# ZX_Gesture_Sensor_SMD_v02.net
KiCad netlist of a schematic drawn in EAGLE
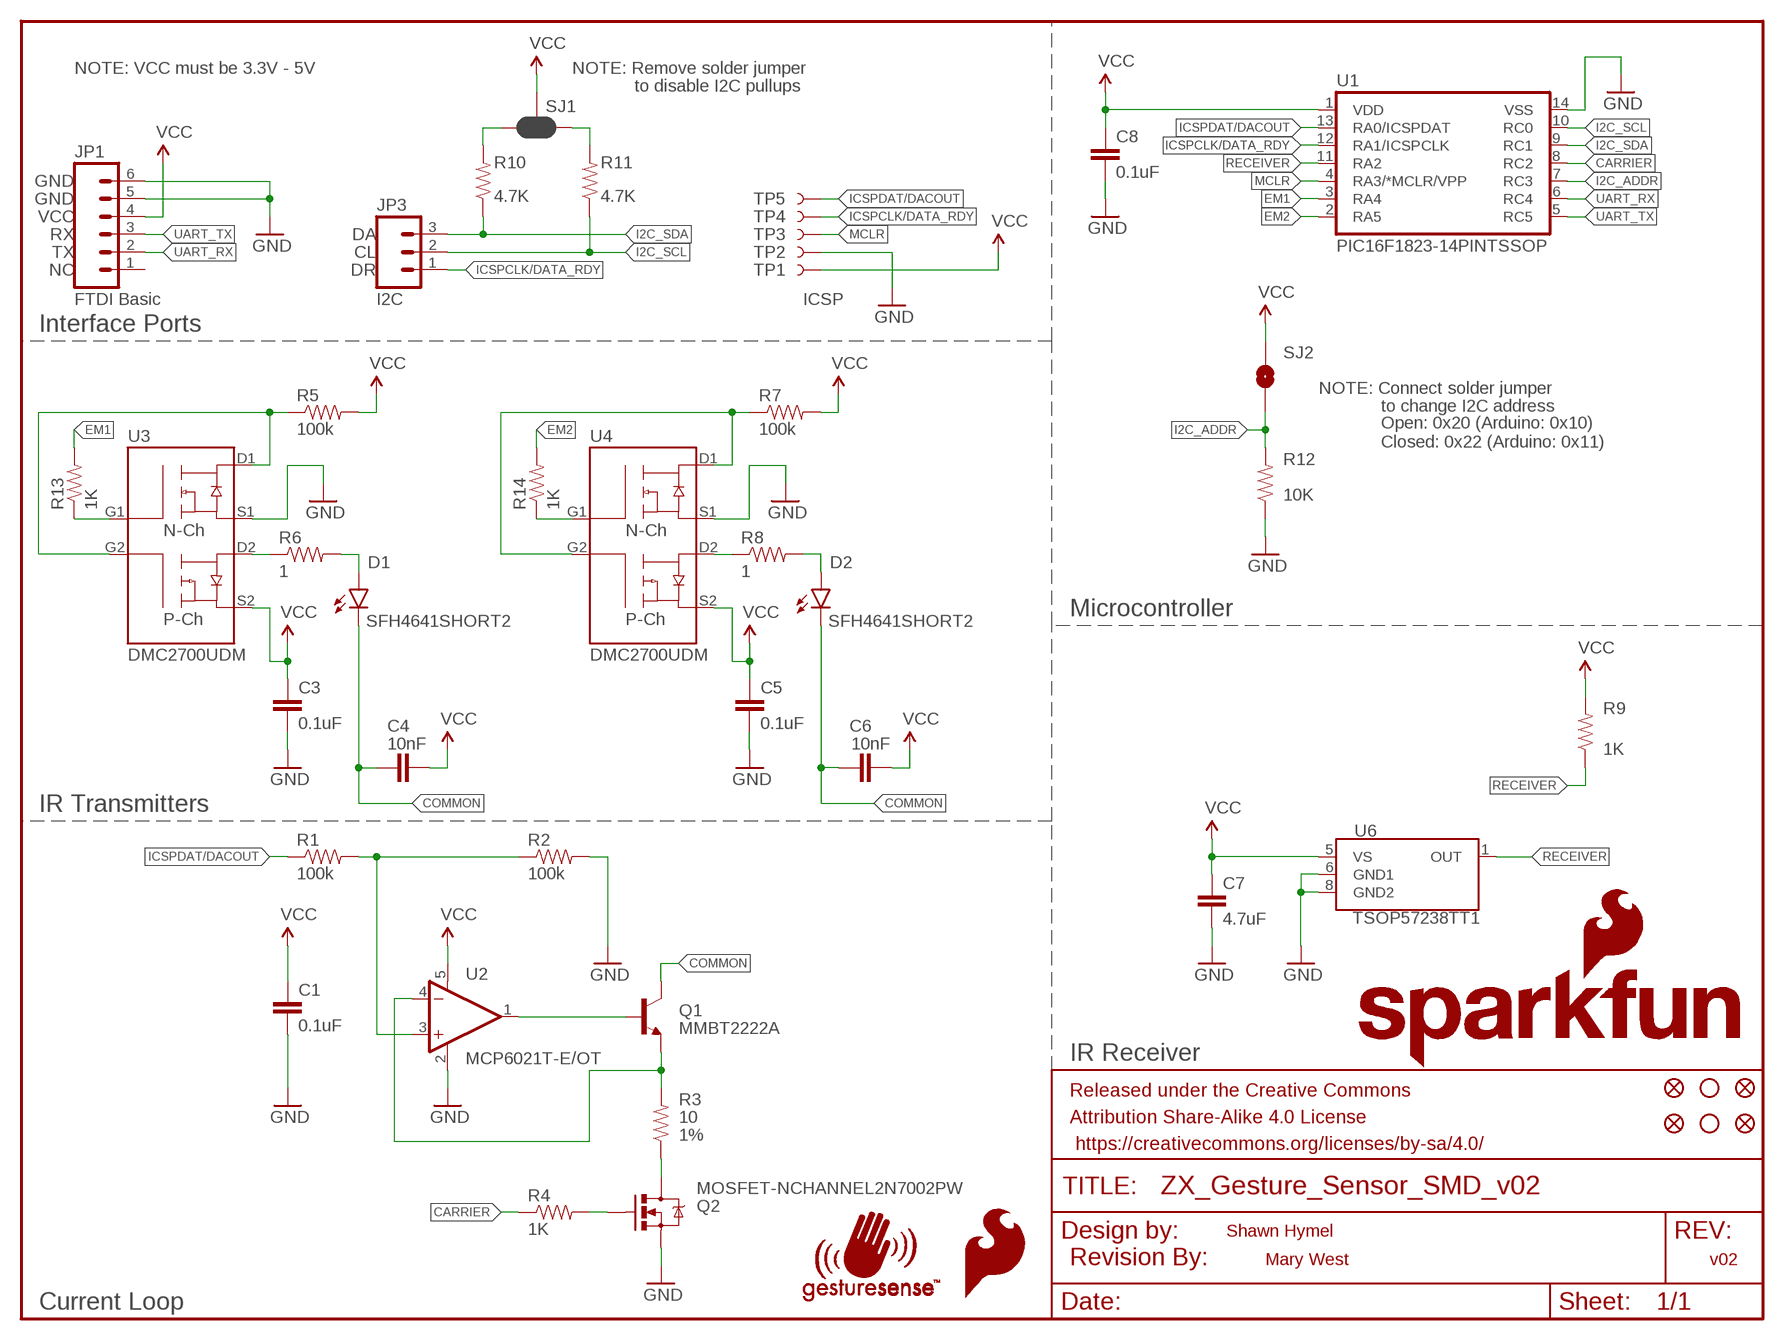
[diagram p0: schematic, sheet 1]

(export (version "E")
  (design (tool "Eeschema 10.0.6"))
  (components
    (comp (ref "C1")
      (value "0.1uF")
      (footprint "eagle-import:0603-CAP")
      (libsource (lib "eagle-import") (part "0.1UF-25V(+80/-20%)(0603)"))
    )
    (comp (ref "C3")
      (value "0.1uF")
      (footprint "eagle-import:0603-CAP")
      (libsource (lib "eagle-import") (part "0.1UF-25V(+80/-20%)(0603)"))
    )
    (comp (ref "C4")
      (value "10nF")
      (footprint "eagle-import:0603-CAP")
      (libsource (lib "eagle-import") (part "10NF/10000PF-50V-10%(0603)"))
    )
    (comp (ref "C5")
      (value "0.1uF")
      (footprint "eagle-import:0603-CAP")
      (libsource (lib "eagle-import") (part "0.1UF-25V(+80/-20%)(0603)"))
    )
    (comp (ref "C6")
      (value "10nF")
      (footprint "eagle-import:0603-CAP")
      (libsource (lib "eagle-import") (part "10NF/10000PF-50V-10%(0603)"))
    )
    (comp (ref "C7")
      (value "4.7uF")
      (footprint "eagle-import:0603-CAP")
      (libsource (lib "eagle-import") (part "4.7UF-6.3V-10%(0603)0603"))
    )
    (comp (ref "C8")
      (value "0.1uF")
      (footprint "eagle-import:0603-CAP")
      (libsource (lib "eagle-import") (part "0.1UF-25V(+80/-20%)(0603)"))
    )
    (comp (ref "D1")
      (value "SFH4641SHORT2")
      (footprint "eagle-import:SFH4641-SHORT2")
      (libsource (lib "eagle-import") (part "SFH4641SHORT2"))
    )
    (comp (ref "D2")
      (value "SFH4641SHORT2")
      (footprint "eagle-import:SFH4641-SHORT2")
      (libsource (lib "eagle-import") (part "SFH4641SHORT2"))
    )
    (comp (ref "FID1")
      (value "FIDUCIALUFIDUCIAL")
      (footprint "eagle-import:MICRO-FIDUCIAL")
      (libsource (lib "eagle-import") (part "FIDUCIALUFIDUCIAL"))
    )
    (comp (ref "FID2")
      (value "FIDUCIALUFIDUCIAL")
      (footprint "eagle-import:MICRO-FIDUCIAL")
      (libsource (lib "eagle-import") (part "FIDUCIALUFIDUCIAL"))
    )
    (comp (ref "FID3")
      (value "FIDUCIALUFIDUCIAL")
      (footprint "eagle-import:MICRO-FIDUCIAL")
      (libsource (lib "eagle-import") (part "FIDUCIALUFIDUCIAL"))
    )
    (comp (ref "FID4")
      (value "FIDUCIALUFIDUCIAL")
      (footprint "eagle-import:MICRO-FIDUCIAL")
      (libsource (lib "eagle-import") (part "FIDUCIALUFIDUCIAL"))
    )
    (comp (ref "FRAME1")
      (value "FRAME-LETTER")
      (footprint "eagle-import:CREATIVE_COMMONS")
      (libsource (lib "eagle-import") (part "FRAME-LETTER"))
    )
    (comp (ref "JP1")
      (value "M06NO_SILK_FEMALE_PTH")
      (footprint "eagle-import:1X06_NO_SILK")
      (libsource (lib "eagle-import") (part "M06NO_SILK_FEMALE_PTH"))
    )
    (comp (ref "JP3")
      (value "M031X03_NO_SILK")
      (footprint "eagle-import:1X03_NO_SILK")
      (libsource (lib "eagle-import") (part "M031X03_NO_SILK"))
    )
    (comp (ref "LOGO1")
      (value "REVISION")
      (footprint "eagle-import:REVISION")
      (libsource (lib "eagle-import") (part "REVISION"))
    )
    (comp (ref "LOGO2")
      (value "SFE_LOGO_FLAME.1_INCH")
      (footprint "eagle-import:SFE_LOGO_FLAME_.1")
      (libsource (lib "eagle-import") (part "SFE_LOGO_FLAME.1_INCH"))
    )
    (comp (ref "Q1")
      (value "MMBT2222A")
      (footprint "eagle-import:SOT23-3")
      (libsource (lib "eagle-import") (part "TRANSISTOR_NPNMMBT2222A"))
    )
    (comp (ref "Q2")
      (value "MOSFET-NCHANNEL2N7002PW")
      (footprint "eagle-import:SOT323")
      (libsource (lib "eagle-import") (part "MOSFET-NCHANNEL2N7002PW"))
    )
    (comp (ref "R1")
      (value "100k")
      (footprint "eagle-import:0603-RES")
      (libsource (lib "eagle-import") (part "100KOHM-1/10W-1%(0603)"))
    )
    (comp (ref "R2")
      (value "100k")
      (footprint "eagle-import:0603-RES")
      (libsource (lib "eagle-import") (part "100KOHM-1/10W-1%(0603)"))
    )
    (comp (ref "R3")
      (value "10")
      (footprint "eagle-import:0603-RES")
      (fields (field (name "TOL") "1%"))
      (libsource (lib "eagle-import") (part "10OHM-1/10W-1%(0603)SMD"))
    )
    (comp (ref "R4")
      (value "1K")
      (footprint "eagle-import:0603-RES")
      (libsource (lib "eagle-import") (part "1KOHM-1/10W-1%(0603)"))
    )
    (comp (ref "R5")
      (value "100k")
      (footprint "eagle-import:0603-RES")
      (libsource (lib "eagle-import") (part "100KOHM-1/10W-1%(0603)"))
    )
    (comp (ref "R6")
      (value "1")
      (footprint "eagle-import:0603-RES")
      (libsource (lib "eagle-import") (part "1OHM1/10W1%(0603)"))
    )
    (comp (ref "R7")
      (value "100k")
      (footprint "eagle-import:0603-RES")
      (libsource (lib "eagle-import") (part "100KOHM-1/10W-1%(0603)"))
    )
    (comp (ref "R8")
      (value "1")
      (footprint "eagle-import:0603-RES")
      (libsource (lib "eagle-import") (part "1OHM1/10W1%(0603)"))
    )
    (comp (ref "R9")
      (value "1K")
      (footprint "eagle-import:0603-RES")
      (libsource (lib "eagle-import") (part "1KOHM-1/10W-1%(0603)"))
    )
    (comp (ref "R10")
      (value "4.7K")
      (footprint "eagle-import:0603-RES")
      (libsource (lib "eagle-import") (part "4.7KOHM-1/10W-1%(0603)"))
    )
    (comp (ref "R11")
      (value "4.7K")
      (footprint "eagle-import:0603-RES")
      (libsource (lib "eagle-import") (part "4.7KOHM-1/10W-1%(0603)"))
    )
    (comp (ref "R12")
      (value "10K")
      (footprint "eagle-import:0603-RES")
      (libsource (lib "eagle-import") (part "10KOHM-1/10W-1%(0603)0603"))
    )
    (comp (ref "R13")
      (value "1K")
      (footprint "eagle-import:0603-RES")
      (libsource (lib "eagle-import") (part "1KOHM-1/10W-1%(0603)"))
    )
    (comp (ref "R14")
      (value "1K")
      (footprint "eagle-import:0603-RES")
      (libsource (lib "eagle-import") (part "1KOHM-1/10W-1%(0603)"))
    )
    (comp (ref "SJ1")
      (value "JUMPER-PAD-3-NC_BY_PASTE")
      (footprint "eagle-import:PAD-JUMPER-3-NC_BY_PASTE_YES_SILK_FULL_BOX")
      (libsource (lib "eagle-import") (part "JUMPER-PAD-3-NC_BY_PASTE"))
    )
    (comp (ref "SJ2")
      (value "JUMPER-PAD-2-NOYES_SILK")
      (footprint "eagle-import:PAD-JUMPER-2-NO_YES_SILK")
      (libsource (lib "eagle-import") (part "JUMPER-PAD-2-NOYES_SILK"))
    )
    (comp (ref "STANDOFF1")
      (value "STAND-OFF")
      (footprint "eagle-import:STAND-OFF")
      (libsource (lib "eagle-import") (part "STAND-OFF"))
    )
    (comp (ref "STANDOFF2")
      (value "STAND-OFF")
      (footprint "eagle-import:STAND-OFF")
      (libsource (lib "eagle-import") (part "STAND-OFF"))
    )
    (comp (ref "TP1")
      (value "TEST-POINT3X4")
      (footprint "eagle-import:PAD.03X.04")
      (libsource (lib "eagle-import") (part "TEST-POINT3X4"))
    )
    (comp (ref "TP2")
      (value "TEST-POINT3X4")
      (footprint "eagle-import:PAD.03X.04")
      (libsource (lib "eagle-import") (part "TEST-POINT3X4"))
    )
    (comp (ref "TP3")
      (value "TEST-POINT3X4")
      (footprint "eagle-import:PAD.03X.04")
      (libsource (lib "eagle-import") (part "TEST-POINT3X4"))
    )
    (comp (ref "TP4")
      (value "TEST-POINT3X4")
      (footprint "eagle-import:PAD.03X.04")
      (libsource (lib "eagle-import") (part "TEST-POINT3X4"))
    )
    (comp (ref "TP5")
      (value "TEST-POINT3X4")
      (footprint "eagle-import:PAD.03X.04")
      (libsource (lib "eagle-import") (part "TEST-POINT3X4"))
    )
    (comp (ref "U$5")
      (value "SFE_LOGO_NAME_FLAME.1_INCH")
      (footprint "eagle-import:SFE_LOGO_NAME_FLAME_.1")
      (libsource (lib "eagle-import") (part "SFE_LOGO_NAME_FLAME.1_INCH"))
    )
    (comp (ref "U$6")
      (value "GESTURESENSE_LOGOSTEXT")
      (footprint "eagle-import:GESTURESENSE_TEXT")
      (libsource (lib "eagle-import") (part "GESTURESENSE_LOGOSTEXT"))
    )
    (comp (ref "U1")
      (value "PIC16F1823-14PINTSSOP")
      (footprint "eagle-import:TSSOP14")
      (libsource (lib "eagle-import") (part "PIC16F1823-14PINTSSOP"))
    )
    (comp (ref "U2")
      (value "MCP6021T-E/OT")
      (footprint "eagle-import:SOT23-5")
      (libsource (lib "eagle-import") (part "MCP6021T-E/OT"))
    )
    (comp (ref "U3")
      (value "DMC2700UDM")
      (footprint "eagle-import:SOT26")
      (libsource (lib "eagle-import") (part "DMC2700UDM"))
    )
    (comp (ref "U4")
      (value "DMC2700UDM")
      (footprint "eagle-import:SOT26")
      (libsource (lib "eagle-import") (part "DMC2700UDM"))
    )
    (comp (ref "U6")
      (value "TSOP57238TT1")
      (footprint "eagle-import:TSOP572")
      (libsource (lib "eagle-import") (part "TSOP57238TT1"))
    )
  )
  (nets
    (net (code "1") (name "CARRIER") (class "Default")
      (node (ref "R4") (pin "1") (pinfunction "1_1") (pintype "passive"))
      (node (ref "U1") (pin "8") (pinfunction "RC2_8") (pintype "bidirectional"))
    )
    (net (code "2") (name "COMMON") (class "Default")
      (node (ref "C4") (pin "1") (pinfunction "1_1") (pintype "passive"))
      (node (ref "C6") (pin "1") (pinfunction "1_1") (pintype "passive"))
      (node (ref "D1") (pin "C") (pinfunction "C_C") (pintype "passive"))
      (node (ref "D2") (pin "C") (pinfunction "C_C") (pintype "passive"))
      (node (ref "Q1") (pin "3") (pinfunction "C_3") (pintype "passive"))
    )
    (net (code "3") (name "EM1") (class "Default")
      (node (ref "R13") (pin "2") (pinfunction "2_2") (pintype "passive"))
      (node (ref "U1") (pin "3") (pinfunction "RA4_3") (pintype "bidirectional"))
    )
    (net (code "4") (name "EM2") (class "Default")
      (node (ref "R14") (pin "2") (pinfunction "2_2") (pintype "passive"))
      (node (ref "U1") (pin "2") (pinfunction "RA5_2") (pintype "bidirectional"))
    )
    (net (code "5") (name "GND") (class "Default")
      (node (ref "C1") (pin "2") (pinfunction "2_2") (pintype "passive"))
      (node (ref "C3") (pin "2") (pinfunction "2_2") (pintype "passive"))
      (node (ref "C5") (pin "2") (pinfunction "2_2") (pintype "passive"))
      (node (ref "C7") (pin "2") (pinfunction "2_2") (pintype "passive"))
      (node (ref "C8") (pin "2") (pinfunction "2_2") (pintype "passive"))
      (node (ref "JP1") (pin "5") (pinfunction "5_5") (pintype "passive"))
      (node (ref "JP1") (pin "6") (pinfunction "6_6") (pintype "passive"))
      (node (ref "Q2") (pin "2") (pinfunction "S_2") (pintype "passive"))
      (node (ref "R12") (pin "1") (pinfunction "1_1") (pintype "passive"))
      (node (ref "R2") (pin "2") (pinfunction "2_2") (pintype "passive"))
      (node (ref "TP2") (pin "P$1") (pinfunction "1_P$1") (pintype "bidirectional"))
      (node (ref "U1") (pin "14") (pinfunction "VSS_14") (pintype "power_in"))
      (node (ref "U2") (pin "2") (pinfunction "V-_2") (pintype "power_in"))
      (node (ref "U3") (pin "S1") (pinfunction "S1_S1") (pintype "bidirectional"))
      (node (ref "U4") (pin "S1") (pinfunction "S1_S1") (pintype "bidirectional"))
      (node (ref "U6") (pin "6") (pinfunction "GND1_6") (pintype "bidirectional"))
      (node (ref "U6") (pin "8") (pinfunction "GND2_8") (pintype "bidirectional"))
    )
    (net (code "6") (name "I2C_ADDR") (class "Default")
      (node (ref "R12") (pin "2") (pinfunction "2_2") (pintype "passive"))
      (node (ref "SJ2") (pin "1") (pinfunction "1_1") (pintype "passive"))
      (node (ref "U1") (pin "7") (pinfunction "RC3_7") (pintype "bidirectional"))
    )
    (net (code "7") (name "I2C_SCL") (class "Default")
      (node (ref "JP3") (pin "2") (pinfunction "2_2") (pintype "passive"))
      (node (ref "R11") (pin "1") (pinfunction "1_1") (pintype "passive"))
      (node (ref "U1") (pin "10") (pinfunction "RC0_10") (pintype "bidirectional"))
    )
    (net (code "8") (name "I2C_SDA") (class "Default")
      (node (ref "JP3") (pin "3") (pinfunction "3_3") (pintype "passive"))
      (node (ref "R10") (pin "1") (pinfunction "1_1") (pintype "passive"))
      (node (ref "U1") (pin "9") (pinfunction "RC1_9") (pintype "bidirectional"))
    )
    (net (code "9") (name "ICSPCLK{slash}DATA_RDY") (class "Default")
      (node (ref "JP3") (pin "1") (pinfunction "1_1") (pintype "passive"))
      (node (ref "TP4") (pin "P$1") (pinfunction "1_P$1") (pintype "bidirectional"))
      (node (ref "U1") (pin "12") (pinfunction "RA1/ICSPCLK_12") (pintype "bidirectional"))
    )
    (net (code "10") (name "ICSPDAT{slash}DACOUT") (class "Default")
      (node (ref "R1") (pin "1") (pinfunction "1_1") (pintype "passive"))
      (node (ref "TP5") (pin "P$1") (pinfunction "1_P$1") (pintype "bidirectional"))
      (node (ref "U1") (pin "13") (pinfunction "RA0/ICSPDAT_13") (pintype "bidirectional"))
    )
    (net (code "11") (name "MCLR") (class "Default")
      (node (ref "TP3") (pin "P$1") (pinfunction "1_P$1") (pintype "bidirectional"))
      (node (ref "U1") (pin "4") (pinfunction "RA3/*MCLR/VPP_4") (pintype "input"))
    )
    (net (code "12") (name "Net-(D1-PadA)") (class "Default")
      (node (ref "D1") (pin "A") (pinfunction "A_A") (pintype "passive"))
      (node (ref "R6") (pin "2") (pinfunction "2_2") (pintype "passive"))
    )
    (net (code "13") (name "Net-(D2-PadA)") (class "Default")
      (node (ref "D2") (pin "A") (pinfunction "A_A") (pintype "passive"))
      (node (ref "R8") (pin "2") (pinfunction "2_2") (pintype "passive"))
    )
    (net (code "14") (name "Net-(Q1-B)") (class "Default")
      (node (ref "Q1") (pin "1") (pinfunction "B_1") (pintype "passive"))
      (node (ref "U2") (pin "1") (pinfunction "OUT_1") (pintype "output"))
    )
    (net (code "15") (name "Net-(Q1-E)") (class "Default")
      (node (ref "Q1") (pin "2") (pinfunction "E_2") (pintype "passive"))
      (node (ref "R3") (pin "2") (pinfunction "2_2") (pintype "passive"))
      (node (ref "U2") (pin "4") (pinfunction "-IN_4") (pintype "input"))
    )
    (net (code "16") (name "Net-(Q2-D)") (class "Default")
      (node (ref "Q2") (pin "3") (pinfunction "D_3") (pintype "passive"))
      (node (ref "R3") (pin "1") (pinfunction "1_1") (pintype "passive"))
    )
    (net (code "17") (name "Net-(Q2-G)") (class "Default")
      (node (ref "Q2") (pin "1") (pinfunction "G_1") (pintype "passive"))
      (node (ref "R4") (pin "2") (pinfunction "2_2") (pintype "passive"))
    )
    (net (code "18") (name "Net-(R5-Pad1)") (class "Default")
      (node (ref "R5") (pin "1") (pinfunction "1_1") (pintype "passive"))
      (node (ref "U3") (pin "D1") (pinfunction "D1_D1") (pintype "bidirectional"))
      (node (ref "U3") (pin "G2") (pinfunction "G2_G2") (pintype "bidirectional"))
    )
    (net (code "19") (name "Net-(R6-Pad1)") (class "Default")
      (node (ref "R6") (pin "1") (pinfunction "1_1") (pintype "passive"))
      (node (ref "U3") (pin "D2") (pinfunction "D2_D2") (pintype "bidirectional"))
    )
    (net (code "20") (name "Net-(R7-Pad1)") (class "Default")
      (node (ref "R7") (pin "1") (pinfunction "1_1") (pintype "passive"))
      (node (ref "U4") (pin "D1") (pinfunction "D1_D1") (pintype "bidirectional"))
      (node (ref "U4") (pin "G2") (pinfunction "G2_G2") (pintype "bidirectional"))
    )
    (net (code "21") (name "Net-(R8-Pad1)") (class "Default")
      (node (ref "R8") (pin "1") (pinfunction "1_1") (pintype "passive"))
      (node (ref "U4") (pin "D2") (pinfunction "D2_D2") (pintype "bidirectional"))
    )
    (net (code "22") (name "Net-(R10-Pad2)") (class "Default")
      (node (ref "R10") (pin "2") (pinfunction "2_2") (pintype "passive"))
      (node (ref "SJ1") (pin "3") (pinfunction "3_3") (pintype "passive"))
    )
    (net (code "23") (name "Net-(R11-Pad2)") (class "Default")
      (node (ref "R11") (pin "2") (pinfunction "2_2") (pintype "passive"))
      (node (ref "SJ1") (pin "1") (pinfunction "1_1") (pintype "passive"))
    )
    (net (code "24") (name "Net-(R13-Pad1)") (class "Default")
      (node (ref "R13") (pin "1") (pinfunction "1_1") (pintype "passive"))
      (node (ref "U3") (pin "G1") (pinfunction "G1_G1") (pintype "bidirectional"))
    )
    (net (code "25") (name "Net-(R14-Pad1)") (class "Default")
      (node (ref "R14") (pin "1") (pinfunction "1_1") (pintype "passive"))
      (node (ref "U4") (pin "G1") (pinfunction "G1_G1") (pintype "bidirectional"))
    )
    (net (code "26") (name "Net-(U2-+IN)") (class "Default")
      (node (ref "R1") (pin "2") (pinfunction "2_2") (pintype "passive"))
      (node (ref "R2") (pin "1") (pinfunction "1_1") (pintype "passive"))
      (node (ref "U2") (pin "3") (pinfunction "+IN_3") (pintype "input"))
    )
    (net (code "27") (name "RECEIVER") (class "Default")
      (node (ref "R9") (pin "1") (pinfunction "1_1") (pintype "passive"))
      (node (ref "U1") (pin "11") (pinfunction "RA2_11") (pintype "bidirectional"))
      (node (ref "U6") (pin "1") (pinfunction "OUT_1") (pintype "bidirectional"))
    )
    (net (code "28") (name "UART_RX") (class "Default")
      (node (ref "JP1") (pin "2") (pinfunction "2_2") (pintype "passive"))
      (node (ref "U1") (pin "6") (pinfunction "RC4_6") (pintype "bidirectional"))
    )
    (net (code "29") (name "UART_TX") (class "Default")
      (node (ref "JP1") (pin "3") (pinfunction "3_3") (pintype "passive"))
      (node (ref "U1") (pin "5") (pinfunction "RC5_5") (pintype "bidirectional"))
    )
    (net (code "30") (name "VCC") (class "Default")
      (node (ref "C1") (pin "1") (pinfunction "1_1") (pintype "passive"))
      (node (ref "C3") (pin "1") (pinfunction "1_1") (pintype "passive"))
      (node (ref "C4") (pin "2") (pinfunction "2_2") (pintype "passive"))
      (node (ref "C5") (pin "1") (pinfunction "1_1") (pintype "passive"))
      (node (ref "C6") (pin "2") (pinfunction "2_2") (pintype "passive"))
      (node (ref "C7") (pin "1") (pinfunction "1_1") (pintype "passive"))
      (node (ref "C8") (pin "1") (pinfunction "1_1") (pintype "passive"))
      (node (ref "JP1") (pin "4") (pinfunction "4_4") (pintype "passive"))
      (node (ref "R5") (pin "2") (pinfunction "2_2") (pintype "passive"))
      (node (ref "R7") (pin "2") (pinfunction "2_2") (pintype "passive"))
      (node (ref "R9") (pin "2") (pinfunction "2_2") (pintype "passive"))
      (node (ref "SJ1") (pin "2") (pinfunction "2_2") (pintype "passive"))
      (node (ref "SJ2") (pin "2") (pinfunction "2_2") (pintype "passive"))
      (node (ref "TP1") (pin "P$1") (pinfunction "1_P$1") (pintype "bidirectional"))
      (node (ref "U1") (pin "1") (pinfunction "VDD_1") (pintype "power_in"))
      (node (ref "U2") (pin "5") (pinfunction "V+_5") (pintype "power_in"))
      (node (ref "U3") (pin "S2") (pinfunction "S2_S2") (pintype "bidirectional"))
      (node (ref "U4") (pin "S2") (pinfunction "S2_S2") (pintype "bidirectional"))
      (node (ref "U6") (pin "5") (pinfunction "VS_5") (pintype "bidirectional"))
    )
    (net (code "31") (name "unconnected-(JP1-Pad1)") (class "Default")
      (node (ref "JP1") (pin "1") (pinfunction "1_1") (pintype "passive"))
    )
  )
)
